# aprs_tracker_v3.net
KiCad netlist of a schematic drawn in EAGLE
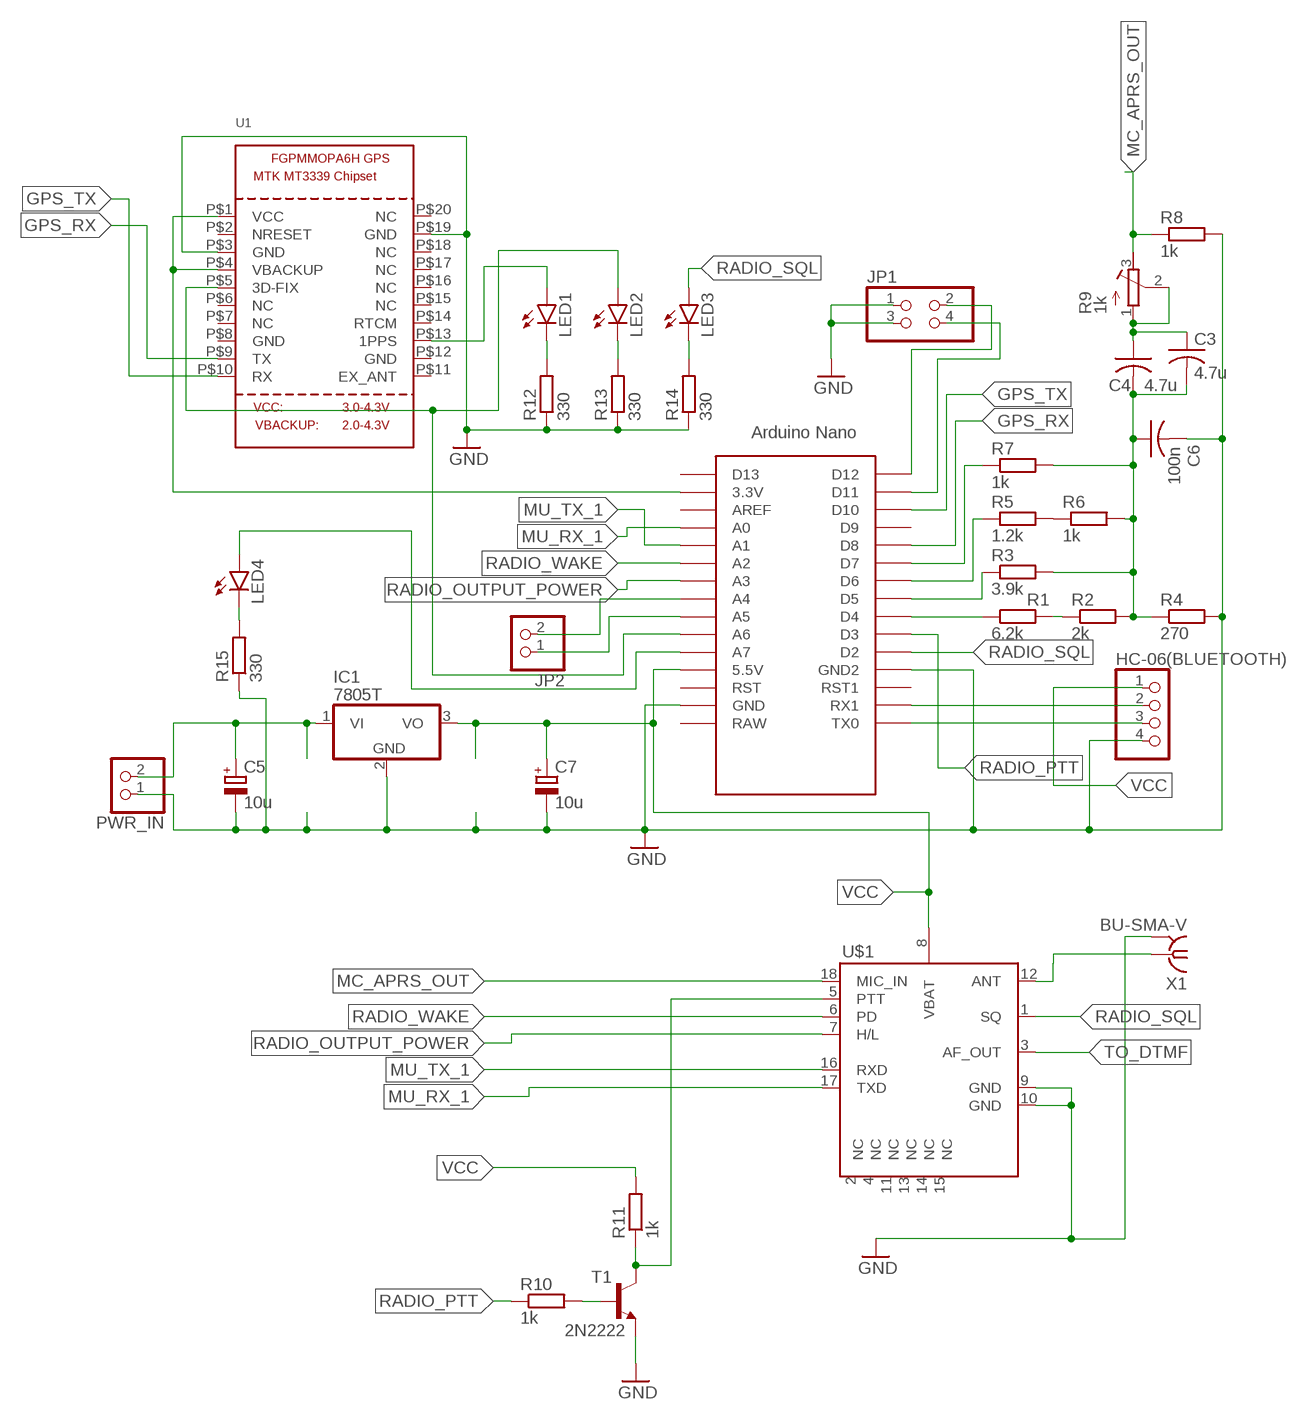
[diagram p0: schematic, sheet 1]

(export (version "E")
  (design (tool "Eeschema 10.0.6"))
  (components
    (comp (ref "C3")
      (value "4.7u")
      (footprint "eagle-import:C050-024X044")
      (libsource (lib "eagle-import") (part "C-US050-024X044"))
    )
    (comp (ref "C4")
      (value "4.7u")
      (footprint "eagle-import:C1206")
      (libsource (lib "eagle-import") (part "C-USC1206"))
    )
    (comp (ref "C5")
      (value "10u")
      (footprint "eagle-import:E5-6")
      (libsource (lib "eagle-import") (part "CPOL-EUE5-6"))
    )
    (comp (ref "C6")
      (value "100n")
      (footprint "eagle-import:C050-024X044")
      (libsource (lib "eagle-import") (part "C-US050-024X044"))
    )
    (comp (ref "C7")
      (value "10u")
      (footprint "eagle-import:E5-6")
      (libsource (lib "eagle-import") (part "CPOL-EUE5-6"))
    )
    (comp (ref "HC-06(BLUETOOTH)")
      (value "PINHD-1X4")
      (footprint "eagle-import:1X04")
      (libsource (lib "eagle-import") (part "PINHD-1X4"))
    )
    (comp (ref "IC1")
      (value "7805T")
      (footprint "eagle-import:TO220H")
      (libsource (lib "eagle-import") (part "78T05"))
    )
    (comp (ref "JP1")
      (value "PINHD-2X2")
      (footprint "eagle-import:2X02")
      (libsource (lib "eagle-import") (part "PINHD-2X2"))
    )
    (comp (ref "JP2")
      (value "PINHD-1X2")
      (footprint "eagle-import:1X02")
      (libsource (lib "eagle-import") (part "PINHD-1X2"))
    )
    (comp (ref "LED1")
      (value "LEDCHIP-LED0805")
      (footprint "eagle-import:CHIP-LED0805")
      (libsource (lib "eagle-import") (part "LEDCHIP-LED0805"))
    )
    (comp (ref "LED2")
      (value "LEDCHIP-LED0805")
      (footprint "eagle-import:CHIP-LED0805")
      (libsource (lib "eagle-import") (part "LEDCHIP-LED0805"))
    )
    (comp (ref "LED3")
      (value "LEDCHIP-LED0805")
      (footprint "eagle-import:CHIP-LED0805")
      (libsource (lib "eagle-import") (part "LEDCHIP-LED0805"))
    )
    (comp (ref "LED4")
      (value "LEDCHIP-LED0805")
      (footprint "eagle-import:CHIP-LED0805")
      (libsource (lib "eagle-import") (part "LEDCHIP-LED0805"))
    )
    (comp (ref "PWR_IN")
      (value "PINHD-1X2")
      (footprint "eagle-import:1X02")
      (libsource (lib "eagle-import") (part "PINHD-1X2"))
    )
    (comp (ref "R1")
      (value "6.2k")
      (footprint "eagle-import:0207_7")
      (libsource (lib "eagle-import") (part "R-EU_0207/7"))
    )
    (comp (ref "R2")
      (value "2k")
      (footprint "eagle-import:0207_7")
      (libsource (lib "eagle-import") (part "R-EU_0207/7"))
    )
    (comp (ref "R3")
      (value "3.9k")
      (footprint "eagle-import:0207_7")
      (libsource (lib "eagle-import") (part "R-EU_0207/7"))
    )
    (comp (ref "R4")
      (value "270")
      (footprint "eagle-import:0204_7")
      (libsource (lib "eagle-import") (part "R-EU_0204/7"))
    )
    (comp (ref "R5")
      (value "1.2k")
      (footprint "eagle-import:0207_7")
      (libsource (lib "eagle-import") (part "R-EU_0207/7"))
    )
    (comp (ref "R6")
      (value "1k")
      (footprint "eagle-import:0207_7")
      (libsource (lib "eagle-import") (part "R-EU_0207/7"))
    )
    (comp (ref "R7")
      (value "1k")
      (footprint "eagle-import:0207_7")
      (libsource (lib "eagle-import") (part "R-EU_0207/7"))
    )
    (comp (ref "R8")
      (value "1k")
      (footprint "eagle-import:0207_7")
      (libsource (lib "eagle-import") (part "R-EU_0207/7"))
    )
    (comp (ref "R9")
      (value "1k")
      (footprint "eagle-import:RTRIM3339P")
      (libsource (lib "eagle-import") (part "R-TRIMM3339P"))
    )
    (comp (ref "R10")
      (value "1k")
      (footprint "eagle-import:0207_7")
      (libsource (lib "eagle-import") (part "R-EU_0207/7"))
    )
    (comp (ref "R11")
      (value "1k")
      (footprint "eagle-import:0207_7")
      (libsource (lib "eagle-import") (part "R-EU_0207/7"))
    )
    (comp (ref "R12")
      (value "330")
      (footprint "eagle-import:R0805")
      (libsource (lib "eagle-import") (part "R-EU_R0805"))
    )
    (comp (ref "R13")
      (value "330")
      (footprint "eagle-import:R0805")
      (libsource (lib "eagle-import") (part "R-EU_R0805"))
    )
    (comp (ref "R14")
      (value "330")
      (footprint "eagle-import:R0805")
      (libsource (lib "eagle-import") (part "R-EU_R0805"))
    )
    (comp (ref "R15")
      (value "330")
      (footprint "eagle-import:R0805")
      (libsource (lib "eagle-import") (part "R-EU_R0805"))
    )
    (comp (ref "T1")
      (value "2N2222")
      (footprint "eagle-import:TO92-EBC-OVAL")
      (libsource (lib "eagle-import") (part "2N2222"))
    )
    (comp (ref "U$1")
      (value "DRA818A")
      (footprint "eagle-import:DRA818A")
      (libsource (lib "eagle-import") (part "DRA818A"))
    )
    (comp (ref "U$4")
      (value "NANO-2")
      (footprint "eagle-import:NANO-NOICSP")
      (libsource (lib "eagle-import") (part "NANO-2"))
    )
    (comp (ref "U1")
      (value "GPS_FGPMMOPA6H")
      (footprint "eagle-import:FGPMMOPA6H")
      (libsource (lib "eagle-import") (part "GPS_FGPMMOPA6H"))
    )
    (comp (ref "X1")
      (value "BU-SMA-V")
      (footprint "eagle-import:BU-SMA-V")
      (libsource (lib "eagle-import") (part "BU-SMA-V"))
    )
  )
  (nets
    (net (code "1") (name "GND") (class "Default")
      (node (ref "C5") (pin "-") (pinfunction "-_-") (pintype "passive"))
      (node (ref "C6") (pin "2") (pinfunction "2_2") (pintype "passive"))
      (node (ref "C7") (pin "-") (pinfunction "-_-") (pintype "passive"))
      (node (ref "HC-06(BLUETOOTH)") (pin "4") (pinfunction "4_4") (pintype "passive"))
      (node (ref "IC1") (pin "2") (pinfunction "GND_2") (pintype "passive"))
      (node (ref "JP1") (pin "1") (pinfunction "1_1") (pintype "passive"))
      (node (ref "JP1") (pin "3") (pinfunction "3_3") (pintype "passive"))
      (node (ref "PWR_IN") (pin "1") (pinfunction "1_1") (pintype "passive"))
      (node (ref "R12") (pin "1") (pinfunction "1_1") (pintype "passive"))
      (node (ref "R13") (pin "1") (pinfunction "1_1") (pintype "passive"))
      (node (ref "R14") (pin "1") (pinfunction "1_1") (pintype "passive"))
      (node (ref "R15") (pin "1") (pinfunction "1_1") (pintype "passive"))
      (node (ref "R4") (pin "2") (pinfunction "2_2") (pintype "passive"))
      (node (ref "R8") (pin "2") (pinfunction "2_2") (pintype "passive"))
      (node (ref "T1") (pin "E") (pinfunction "E_E") (pintype "passive"))
      (node (ref "U$1") (pin "10") (pinfunction "GND_10") (pintype "bidirectional"))
      (node (ref "U$1") (pin "9") (pinfunction "GND_9") (pintype "bidirectional"))
      (node (ref "U$4") (pin "GND") (pinfunction "GND_GND") (pintype "bidirectional"))
      (node (ref "U$4") (pin "GND1") (pinfunction "GND2_GND1") (pintype "bidirectional"))
      (node (ref "U1") (pin "P$19") (pinfunction "GND_P$19") (pintype "bidirectional"))
      (node (ref "U1") (pin "P$3") (pinfunction "GND_P$3") (pintype "bidirectional"))
      (node (ref "X1") (pin "2") (pinfunction "2_2") (pintype "passive"))
      (node (ref "X1") (pin "3") (pinfunction "2_3") (pintype "passive"))
      (node (ref "X1") (pin "4") (pinfunction "2_4") (pintype "passive"))
      (node (ref "X1") (pin "5") (pinfunction "2_5") (pintype "passive"))
    )
    (net (code "2") (name "GPS_RX") (class "Default")
      (node (ref "U$4") (pin "D8") (pinfunction "D8_D8") (pintype "bidirectional"))
      (node (ref "U1") (pin "P$9") (pinfunction "TX_P$9") (pintype "bidirectional"))
    )
    (net (code "3") (name "GPS_TX") (class "Default")
      (node (ref "U$4") (pin "D10") (pinfunction "D10_D10") (pintype "bidirectional"))
      (node (ref "U1") (pin "P$10") (pinfunction "RX_P$10") (pintype "bidirectional"))
    )
    (net (code "4") (name "MC_APRS_OUT") (class "Default")
      (node (ref "R8") (pin "1") (pinfunction "1_1") (pintype "passive"))
      (node (ref "R9") (pin "3") (pinfunction "E_3") (pintype "passive"))
      (node (ref "U$1") (pin "18") (pinfunction "MIC_IN_18") (pintype "bidirectional"))
    )
    (net (code "5") (name "MU_RX_1") (class "Default")
      (node (ref "U$1") (pin "17") (pinfunction "TXD_17") (pintype "bidirectional"))
      (node (ref "U$4") (pin "A0") (pinfunction "A0_A0") (pintype "bidirectional"))
    )
    (net (code "6") (name "MU_TX_1") (class "Default")
      (node (ref "U$1") (pin "16") (pinfunction "RXD_16") (pintype "bidirectional"))
      (node (ref "U$4") (pin "A1") (pinfunction "A1_A1") (pintype "bidirectional"))
    )
    (net (code "7") (name "Net-(C3-Pad2)") (class "Default")
      (node (ref "C3") (pin "2") (pinfunction "2_2") (pintype "passive"))
      (node (ref "C4") (pin "2") (pinfunction "2_2") (pintype "passive"))
      (node (ref "C6") (pin "1") (pinfunction "1_1") (pintype "passive"))
      (node (ref "R2") (pin "2") (pinfunction "2_2") (pintype "passive"))
      (node (ref "R3") (pin "2") (pinfunction "2_2") (pintype "passive"))
      (node (ref "R4") (pin "1") (pinfunction "1_1") (pintype "passive"))
      (node (ref "R6") (pin "2") (pinfunction "2_2") (pintype "passive"))
      (node (ref "R7") (pin "2") (pinfunction "2_2") (pintype "passive"))
    )
    (net (code "8") (name "Net-(HC-06(BLUETOOTH)-Pad2)") (class "Default")
      (node (ref "HC-06(BLUETOOTH)") (pin "2") (pinfunction "2_2") (pintype "passive"))
      (node (ref "U$4") (pin "RX1") (pinfunction "RX1_RX1") (pintype "bidirectional"))
    )
    (net (code "9") (name "Net-(HC-06(BLUETOOTH)-Pad3)") (class "Default")
      (node (ref "HC-06(BLUETOOTH)") (pin "3") (pinfunction "3_3") (pintype "passive"))
      (node (ref "U$4") (pin "TX0") (pinfunction "TX0_TX0") (pintype "bidirectional"))
    )
    (net (code "10") (name "Net-(IC1-VI)") (class "Default")
      (node (ref "C5") (pin "+") (pinfunction "+_+") (pintype "passive"))
      (node (ref "IC1") (pin "1") (pinfunction "VI_1") (pintype "input"))
      (node (ref "PWR_IN") (pin "2") (pinfunction "2_2") (pintype "passive"))
    )
    (net (code "11") (name "Net-(JP1-Pad2)") (class "Default")
      (node (ref "JP1") (pin "2") (pinfunction "2_2") (pintype "passive"))
      (node (ref "U$4") (pin "D12") (pinfunction "D12_D12") (pintype "bidirectional"))
    )
    (net (code "12") (name "Net-(JP1-Pad4)") (class "Default")
      (node (ref "JP1") (pin "4") (pinfunction "4_4") (pintype "passive"))
      (node (ref "U$4") (pin "D11") (pinfunction "D11_D11") (pintype "bidirectional"))
    )
    (net (code "13") (name "Net-(JP2-Pad1)") (class "Default")
      (node (ref "JP2") (pin "1") (pinfunction "1_1") (pintype "passive"))
      (node (ref "U$4") (pin "A5") (pinfunction "A5_A5") (pintype "bidirectional"))
    )
    (net (code "14") (name "Net-(JP2-Pad2)") (class "Default")
      (node (ref "JP2") (pin "2") (pinfunction "2_2") (pintype "passive"))
      (node (ref "U$4") (pin "A4") (pinfunction "A4_A4") (pintype "bidirectional"))
    )
    (net (code "15") (name "Net-(LED1-PadC)") (class "Default")
      (node (ref "LED1") (pin "C") (pinfunction "C_C") (pintype "passive"))
      (node (ref "R12") (pin "2") (pinfunction "2_2") (pintype "passive"))
    )
    (net (code "16") (name "Net-(LED2-PadC)") (class "Default")
      (node (ref "LED2") (pin "C") (pinfunction "C_C") (pintype "passive"))
      (node (ref "R13") (pin "2") (pinfunction "2_2") (pintype "passive"))
    )
    (net (code "17") (name "Net-(LED3-PadC)") (class "Default")
      (node (ref "LED3") (pin "C") (pinfunction "C_C") (pintype "passive"))
      (node (ref "R14") (pin "2") (pinfunction "2_2") (pintype "passive"))
    )
    (net (code "18") (name "Net-(LED4-PadA)") (class "Default")
      (node (ref "LED4") (pin "A") (pinfunction "A_A") (pintype "passive"))
      (node (ref "U$4") (pin "A7") (pinfunction "A7_A7") (pintype "bidirectional"))
    )
    (net (code "19") (name "Net-(LED4-PadC)") (class "Default")
      (node (ref "LED4") (pin "C") (pinfunction "C_C") (pintype "passive"))
      (node (ref "R15") (pin "2") (pinfunction "2_2") (pintype "passive"))
    )
    (net (code "20") (name "Net-(R1-Pad1)") (class "Default")
      (node (ref "R1") (pin "1") (pinfunction "1_1") (pintype "passive"))
      (node (ref "U$4") (pin "D4") (pinfunction "D4_D4") (pintype "bidirectional"))
    )
    (net (code "21") (name "Net-(R1-Pad2)") (class "Default")
      (node (ref "R1") (pin "2") (pinfunction "2_2") (pintype "passive"))
      (node (ref "R2") (pin "1") (pinfunction "1_1") (pintype "passive"))
    )
    (net (code "22") (name "Net-(R3-Pad1)") (class "Default")
      (node (ref "R3") (pin "1") (pinfunction "1_1") (pintype "passive"))
      (node (ref "U$4") (pin "D5") (pinfunction "D5_D5") (pintype "bidirectional"))
    )
    (net (code "23") (name "Net-(R5-Pad1)") (class "Default")
      (node (ref "R5") (pin "1") (pinfunction "1_1") (pintype "passive"))
      (node (ref "U$4") (pin "D6") (pinfunction "D6_D6") (pintype "bidirectional"))
    )
    (net (code "24") (name "Net-(R5-Pad2)") (class "Default")
      (node (ref "R5") (pin "2") (pinfunction "2_2") (pintype "passive"))
      (node (ref "R6") (pin "1") (pinfunction "1_1") (pintype "passive"))
    )
    (net (code "25") (name "Net-(R7-Pad1)") (class "Default")
      (node (ref "R7") (pin "1") (pinfunction "1_1") (pintype "passive"))
      (node (ref "U$4") (pin "D7") (pinfunction "D7_D7") (pintype "bidirectional"))
    )
    (net (code "26") (name "Net-(R9-A)") (class "Default")
      (node (ref "C3") (pin "1") (pinfunction "1_1") (pintype "passive"))
      (node (ref "C4") (pin "1") (pinfunction "1_1") (pintype "passive"))
      (node (ref "R9") (pin "1") (pinfunction "A_1") (pintype "passive"))
      (node (ref "R9") (pin "2") (pinfunction "S_2") (pintype "passive"))
    )
    (net (code "27") (name "Net-(R10-Pad2)") (class "Default")
      (node (ref "R10") (pin "2") (pinfunction "2_2") (pintype "passive"))
      (node (ref "T1") (pin "B") (pinfunction "B_B") (pintype "passive"))
    )
    (net (code "28") (name "Net-(U$1-ANT)") (class "Default")
      (node (ref "U$1") (pin "12") (pinfunction "ANT_12") (pintype "bidirectional"))
      (node (ref "X1") (pin "1") (pinfunction "1_1") (pintype "passive"))
    )
    (net (code "29") (name "Net-(U$1-PTT)") (class "Default")
      (node (ref "R11") (pin "1") (pinfunction "1_1") (pintype "passive"))
      (node (ref "T1") (pin "C") (pinfunction "C_C") (pintype "passive"))
      (node (ref "U$1") (pin "5") (pinfunction "PTT_5") (pintype "bidirectional"))
    )
    (net (code "30") (name "Net-(U1-1PPS)") (class "Default")
      (node (ref "LED1") (pin "A") (pinfunction "A_A") (pintype "passive"))
      (node (ref "U1") (pin "P$13") (pinfunction "1PPS_P$13") (pintype "bidirectional"))
    )
    (net (code "31") (name "Net-(U1-3D-FIX)") (class "Default")
      (node (ref "LED2") (pin "A") (pinfunction "A_A") (pintype "passive"))
      (node (ref "U$4") (pin "A6") (pinfunction "A6_A6") (pintype "bidirectional"))
      (node (ref "U1") (pin "P$5") (pinfunction "3D-FIX_P$5") (pintype "bidirectional"))
    )
    (net (code "32") (name "Net-(U1-VBACKUP)") (class "Default")
      (node (ref "U$4") (pin "3.3V") (pinfunction "3.3V_3.3V") (pintype "bidirectional"))
      (node (ref "U1") (pin "P$1") (pinfunction "VCC_P$1") (pintype "bidirectional"))
      (node (ref "U1") (pin "P$4") (pinfunction "VBACKUP_P$4") (pintype "bidirectional"))
    )
    (net (code "33") (name "RADIO_OUTPUT_POWER") (class "Default")
      (node (ref "U$1") (pin "7") (pinfunction "H/L_7") (pintype "bidirectional"))
      (node (ref "U$4") (pin "A3") (pinfunction "A3_A3") (pintype "bidirectional"))
    )
    (net (code "34") (name "RADIO_PTT") (class "Default")
      (node (ref "R10") (pin "1") (pinfunction "1_1") (pintype "passive"))
      (node (ref "U$4") (pin "D3") (pinfunction "D3_D3") (pintype "bidirectional"))
    )
    (net (code "35") (name "RADIO_SQL") (class "Default")
      (node (ref "LED3") (pin "A") (pinfunction "A_A") (pintype "passive"))
      (node (ref "U$1") (pin "1") (pinfunction "SQ_1") (pintype "bidirectional"))
      (node (ref "U$4") (pin "D2") (pinfunction "D2_D2") (pintype "bidirectional"))
    )
    (net (code "36") (name "RADIO_WAKE") (class "Default")
      (node (ref "U$1") (pin "6") (pinfunction "PD_6") (pintype "bidirectional"))
      (node (ref "U$4") (pin "A2") (pinfunction "A2_A2") (pintype "bidirectional"))
    )
    (net (code "37") (name "TO_DTMF") (class "Default")
      (node (ref "U$1") (pin "3") (pinfunction "AF_OUT_3") (pintype "bidirectional"))
    )
    (net (code "38") (name "VCC") (class "Default")
      (node (ref "C7") (pin "+") (pinfunction "+_+") (pintype "passive"))
      (node (ref "HC-06(BLUETOOTH)") (pin "1") (pinfunction "1_1") (pintype "passive"))
      (node (ref "IC1") (pin "3") (pinfunction "VO_3") (pintype "passive"))
      (node (ref "R11") (pin "2") (pinfunction "2_2") (pintype "passive"))
      (node (ref "U$1") (pin "8") (pinfunction "VBAT_8") (pintype "bidirectional"))
      (node (ref "U$4") (pin "5V") (pinfunction "5.5V_5V") (pintype "bidirectional"))
    )
    (net (code "39") (name "unconnected-(U$1-NC-Pad2)") (class "Default")
      (node (ref "U$1") (pin "2") (pinfunction "NC_2") (pintype "bidirectional"))
    )
    (net (code "40") (name "unconnected-(U$1-NC-Pad4)") (class "Default")
      (node (ref "U$1") (pin "4") (pinfunction "NC_4") (pintype "bidirectional"))
    )
    (net (code "41") (name "unconnected-(U$1-NC-Pad11)") (class "Default")
      (node (ref "U$1") (pin "11") (pinfunction "NC_11") (pintype "bidirectional"))
    )
    (net (code "42") (name "unconnected-(U$1-NC-Pad13)") (class "Default")
      (node (ref "U$1") (pin "13") (pinfunction "NC_13") (pintype "bidirectional"))
    )
    (net (code "43") (name "unconnected-(U$1-NC-Pad14)") (class "Default")
      (node (ref "U$1") (pin "14") (pinfunction "NC_14") (pintype "bidirectional"))
    )
    (net (code "44") (name "unconnected-(U$1-NC-Pad15)") (class "Default")
      (node (ref "U$1") (pin "15") (pinfunction "NC_15") (pintype "bidirectional"))
    )
    (net (code "45") (name "unconnected-(U$4-ICSP1-PadP$1)") (class "Default")
      (node (ref "U$4") (pin "P$1") (pinfunction "ICSP1_P$1") (pintype "bidirectional"))
    )
    (net (code "46") (name "unconnected-(U$4-ICSP2-PadP$2)") (class "Default")
      (node (ref "U$4") (pin "P$2") (pinfunction "ICSP2_P$2") (pintype "bidirectional"))
    )
    (net (code "47") (name "unconnected-(U$4-ICSP3-PadP$3)") (class "Default")
      (node (ref "U$4") (pin "P$3") (pinfunction "ICSP3_P$3") (pintype "bidirectional"))
    )
    (net (code "48") (name "unconnected-(U$4-ICSP4-PadP$4)") (class "Default")
      (node (ref "U$4") (pin "P$4") (pinfunction "ICSP4_P$4") (pintype "bidirectional"))
    )
    (net (code "49") (name "unconnected-(U$4-ICSP5-PadP$5)") (class "Default")
      (node (ref "U$4") (pin "P$5") (pinfunction "ICSP5_P$5") (pintype "bidirectional"))
    )
    (net (code "50") (name "unconnected-(U$4-ICSP6-PadP$6)") (class "Default")
      (node (ref "U$4") (pin "P$6") (pinfunction "ICSP6_P$6") (pintype "bidirectional"))
    )
    (net (code "51") (name "unconnected-(U$4-PadAREF)") (class "Default")
      (node (ref "U$4") (pin "AREF") (pinfunction "AREF_AREF") (pintype "bidirectional"))
    )
    (net (code "52") (name "unconnected-(U$4-PadD9)") (class "Default")
      (node (ref "U$4") (pin "D9") (pinfunction "D9_D9") (pintype "bidirectional"))
    )
    (net (code "53") (name "unconnected-(U$4-PadD13)") (class "Default")
      (node (ref "U$4") (pin "D13") (pinfunction "D13_D13") (pintype "bidirectional"))
    )
    (net (code "54") (name "unconnected-(U$4-PadRAW)") (class "Default")
      (node (ref "U$4") (pin "RAW") (pinfunction "RAW_RAW") (pintype "bidirectional"))
    )
    (net (code "55") (name "unconnected-(U$4-PadRST)") (class "Default")
      (node (ref "U$4") (pin "RST") (pinfunction "RST_RST") (pintype "bidirectional"))
    )
    (net (code "56") (name "unconnected-(U$4-PadRST1)") (class "Default")
      (node (ref "U$4") (pin "RST1") (pinfunction "RST1_RST1") (pintype "bidirectional"))
    )
    (net (code "57") (name "unconnected-(U1-EX_ANT-PadP$11)") (class "Default")
      (node (ref "U1") (pin "P$11") (pinfunction "EX_ANT_P$11") (pintype "bidirectional"))
    )
    (net (code "58") (name "unconnected-(U1-GND-PadP$8)") (class "Default")
      (node (ref "U1") (pin "P$8") (pinfunction "GND_P$8") (pintype "bidirectional"))
    )
    (net (code "59") (name "unconnected-(U1-GND-PadP$12)") (class "Default")
      (node (ref "U1") (pin "P$12") (pinfunction "GND_P$12") (pintype "bidirectional"))
    )
    (net (code "60") (name "unconnected-(U1-NC-PadP$6)") (class "Default")
      (node (ref "U1") (pin "P$6") (pinfunction "NC_P$6") (pintype "bidirectional"))
    )
    (net (code "61") (name "unconnected-(U1-NC-PadP$7)") (class "Default")
      (node (ref "U1") (pin "P$7") (pinfunction "NC_P$7") (pintype "bidirectional"))
    )
    (net (code "62") (name "unconnected-(U1-NC-PadP$15)") (class "Default")
      (node (ref "U1") (pin "P$15") (pinfunction "NC_P$15") (pintype "bidirectional"))
    )
    (net (code "63") (name "unconnected-(U1-NC-PadP$16)") (class "Default")
      (node (ref "U1") (pin "P$16") (pinfunction "NC_P$16") (pintype "bidirectional"))
    )
    (net (code "64") (name "unconnected-(U1-NC-PadP$17)") (class "Default")
      (node (ref "U1") (pin "P$17") (pinfunction "NC_P$17") (pintype "bidirectional"))
    )
    (net (code "65") (name "unconnected-(U1-NC-PadP$18)") (class "Default")
      (node (ref "U1") (pin "P$18") (pinfunction "NC_P$18") (pintype "bidirectional"))
    )
    (net (code "66") (name "unconnected-(U1-NC-PadP$20)") (class "Default")
      (node (ref "U1") (pin "P$20") (pinfunction "NC_P$20") (pintype "bidirectional"))
    )
    (net (code "67") (name "unconnected-(U1-NRESET-PadP$2)") (class "Default")
      (node (ref "U1") (pin "P$2") (pinfunction "NRESET_P$2") (pintype "bidirectional"))
    )
    (net (code "68") (name "unconnected-(U1-RTCM-PadP$14)") (class "Default")
      (node (ref "U1") (pin "P$14") (pinfunction "RTCM_P$14") (pintype "bidirectional"))
    )
  )
)
